# 1-Schematic_TRIAC_Dimmer.net
KiCad netlist of a schematic drawn in EasyEDA
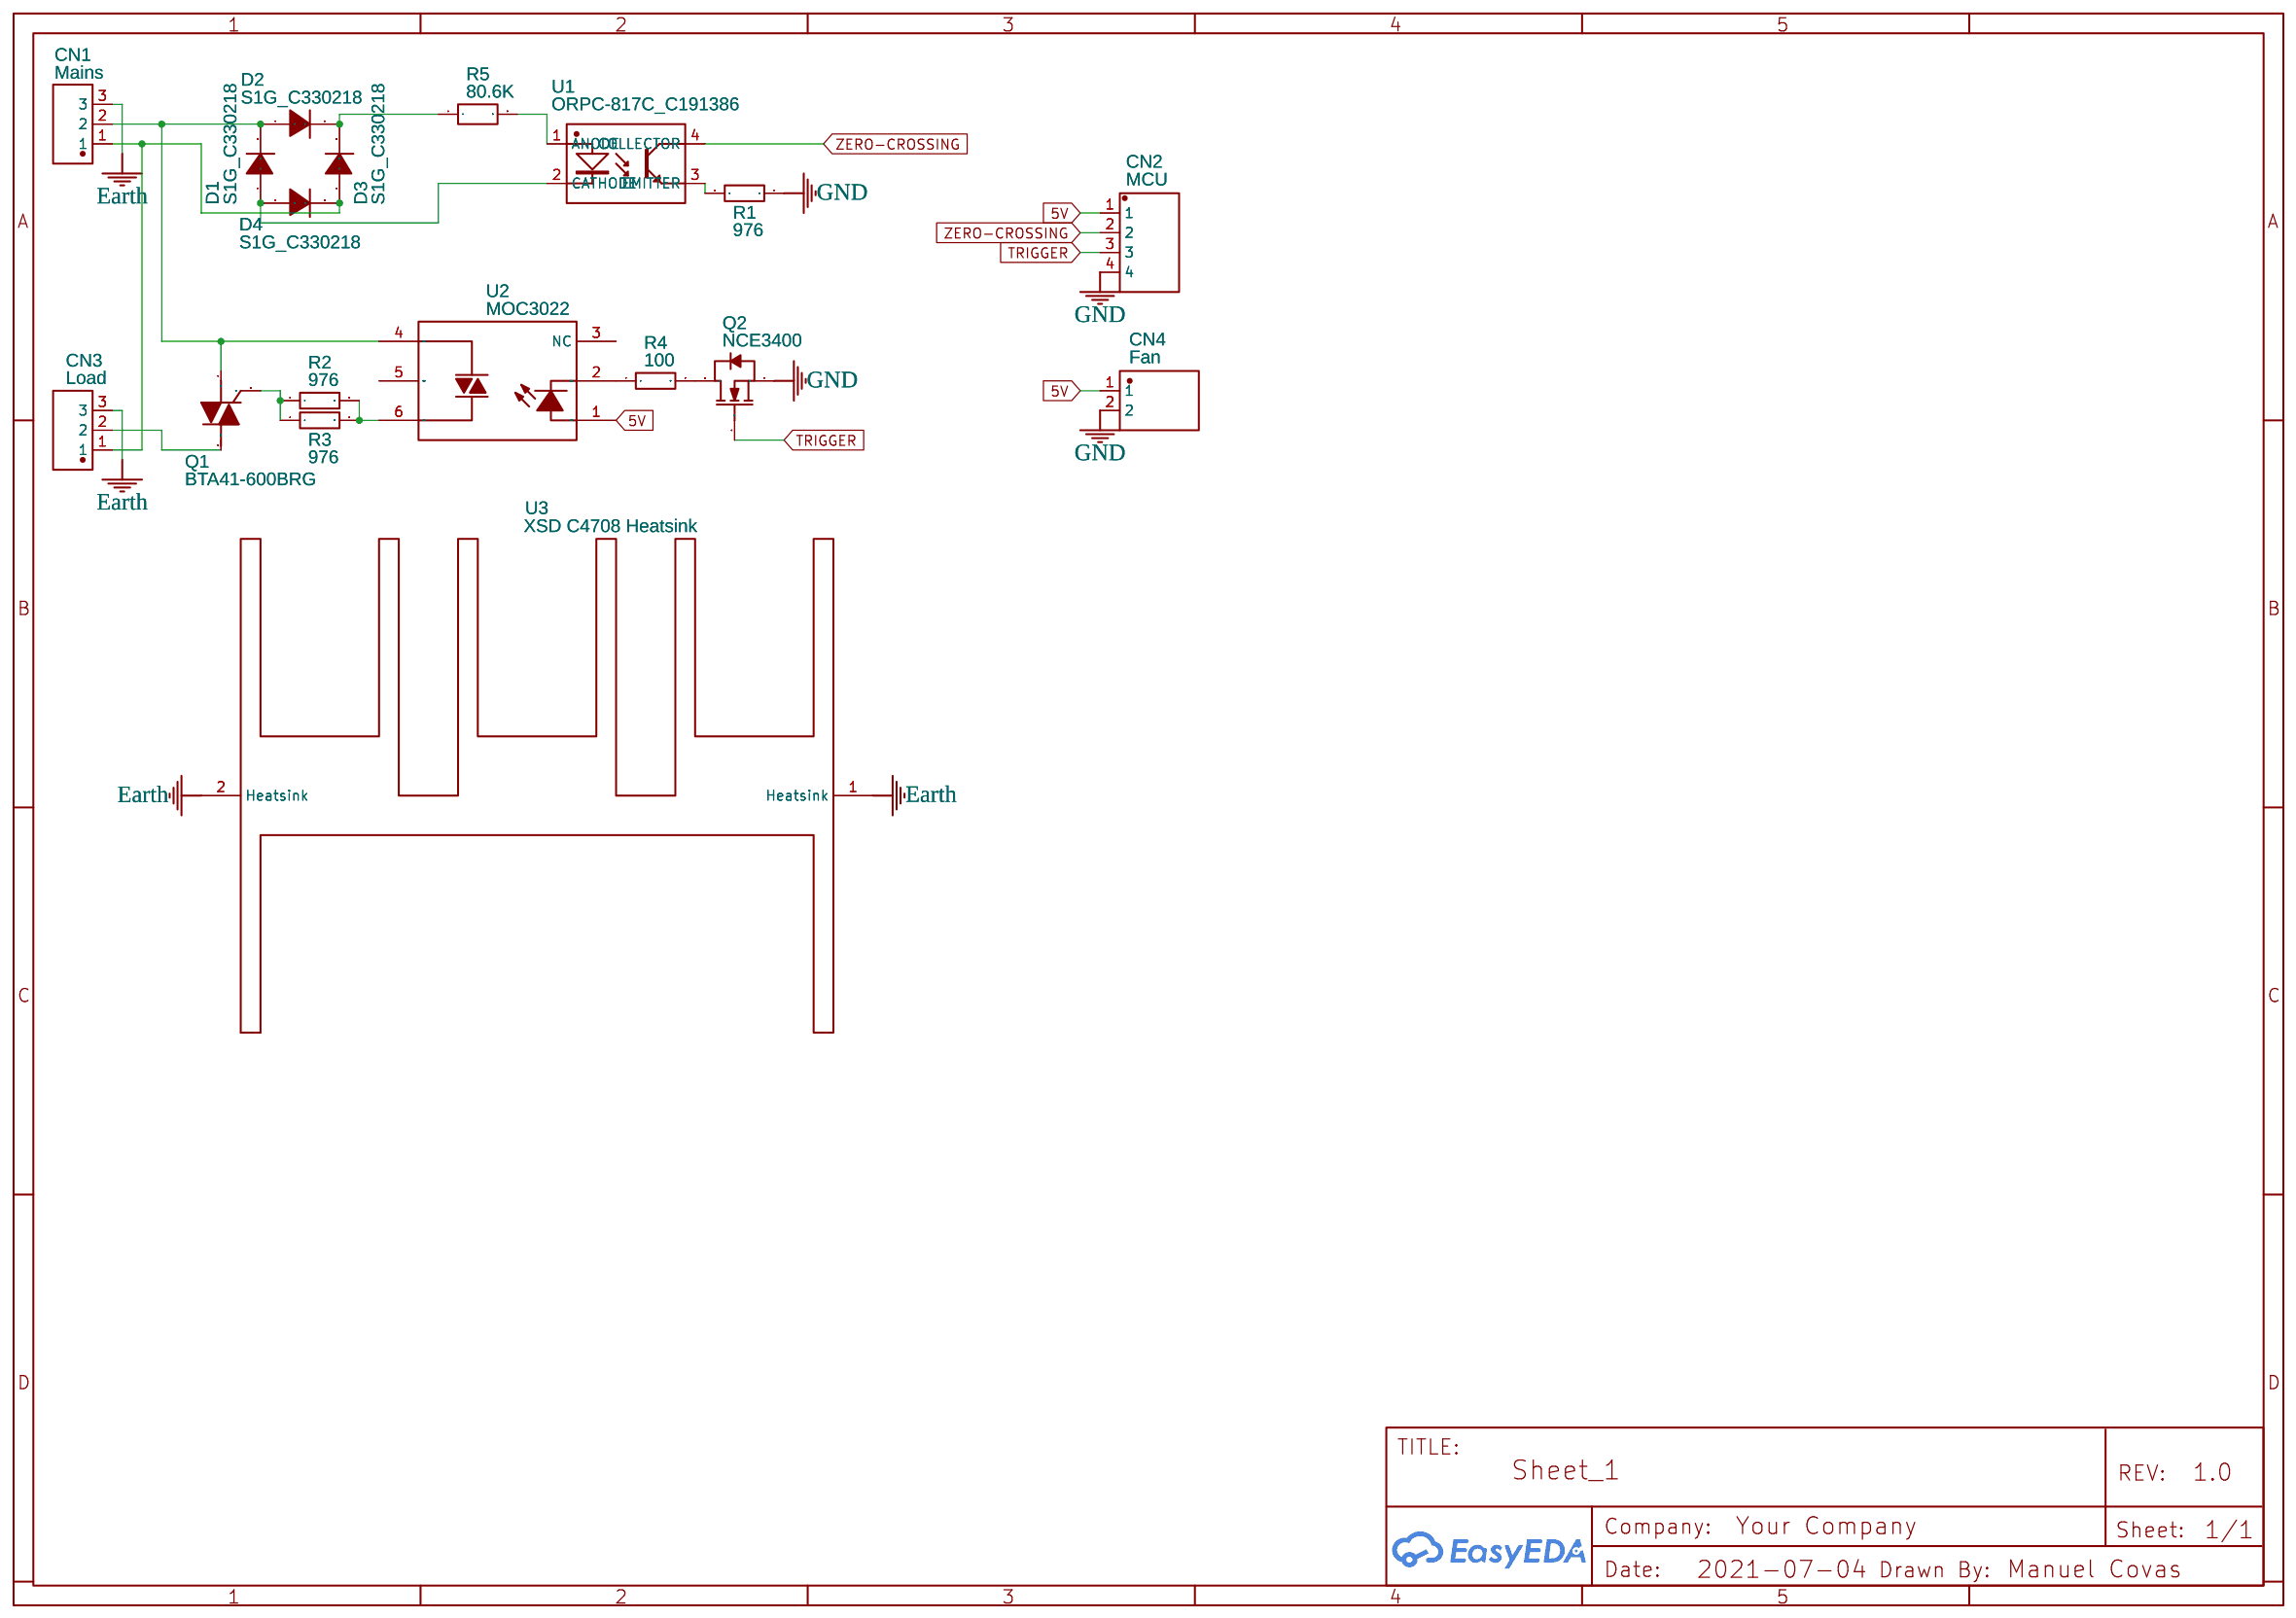
[diagram p0: schematic sheet]

(export (version "E")
  (design (tool "Eeschema 10.0.6"))
  (components
    (comp (ref "CN1")
      (value "Mains")
      (fields
        (field (name "BOM_Manufacturer Part") "KF301-5.0-3P")
        (field (name "BOM_Supplier Part") "C474882")
      )
      (libsource (lib "") (part "KF301-5.0-3P"))
    )
    (comp (ref "CN2")
      (value "MCU")
      (fields
        (field (name "BOM_Manufacturer Part") "B4B-XH-AM(LF)(SN)")
        (field (name "BOM_Supplier Part") "C161871")
      )
      (libsource (lib "") (part "B4B-XH-AM(LF)(SN)"))
    )
    (comp (ref "CN3")
      (value "Load")
      (fields
        (field (name "BOM_Manufacturer Part") "KF301-5.0-3P")
        (field (name "BOM_Supplier Part") "C474882")
      )
      (libsource (lib "") (part "KF301-5.0-3P"))
    )
    (comp (ref "CN4")
      (value "Fan")
      (fields (field (name "BOM_Supplier Part") "C161869"))
      (libsource (lib "") (part "B2B-XH-AM (LF)(SN)"))
    )
    (comp (ref "D1")
      (value "S1G_C330218")
      (fields (field (name "BOM_Supplier Part") "C330218"))
      (libsource (lib "") (part "S1G_C330218_1"))
    )
    (comp (ref "D2")
      (value "S1G_C330218")
      (fields (field (name "BOM_Supplier Part") "C330218"))
      (libsource (lib "") (part "S1G_C330218"))
    )
    (comp (ref "D3")
      (value "S1G_C330218")
      (fields (field (name "BOM_Supplier Part") "C330218"))
      (libsource (lib "") (part "S1G_C330218_1"))
    )
    (comp (ref "D4")
      (value "S1G_C330218")
      (fields (field (name "BOM_Supplier Part") "C330218"))
      (libsource (lib "") (part "S1G_C330218"))
    )
    (comp (ref "Q1")
      (value "BTA41-600BRG")
      (fields (field (name "BOM_Supplier Part") "C9103"))
      (libsource (lib "") (part "BTA41-600BRG"))
    )
    (comp (ref "Q2")
      (value "NCE3400")
      (fields (field (name "BOM_Supplier Part") "C113202"))
      (libsource (lib "") (part "NCE3400"))
    )
    (comp (ref "R1")
      (value "976")
      (fields
        (field (name "BOM_Manufacturer Part") "AC1206FR-07976RL")
        (field (name "BOM_Supplier Part") "C229856")
      )
      (libsource (lib "") (part "AC1206FR-07976RL_1"))
    )
    (comp (ref "R2")
      (value "976")
      (fields
        (field (name "BOM_Manufacturer Part") "AC1206FR-07976RL")
        (field (name "BOM_Supplier Part") "C229856")
      )
      (libsource (lib "") (part "AC1206FR-07976RL"))
    )
    (comp (ref "R3")
      (value "976")
      (fields
        (field (name "BOM_Manufacturer Part") "AC1206FR-07976RL")
        (field (name "BOM_Supplier Part") "C229856")
      )
      (libsource (lib "") (part "AC1206FR-07976RL"))
    )
    (comp (ref "R4")
      (value "100")
      (fields
        (field (name "BOM_Manufacturer Part") "RMC1/10K101FTP")
        (field (name "BOM_Supplier Part") "C340501")
      )
      (libsource (lib "") (part "RMC1/10K101FTP"))
    )
    (comp (ref "R5")
      (value "80.6K")
      (fields
        (field (name "BOM_Manufacturer Part") "25121WF8062T4E")
        (field (name "BOM_Supplier Part") "C406917")
      )
      (libsource (lib "") (part "25121WF8062T4E"))
    )
    (comp (ref "U1")
      (value "ORPC-817C_C191386")
      (fields (field (name "BOM_Manufacturer Part") "ORPC-817C") (field (name "BOM_Supplier Part") "C191386"))
      (libsource (lib "") (part "ORPC-817C_C191386"))
    )
    (comp (ref "U2")
      (value "MOC3022")
      (fields (field (name "BOM_Supplier Part") "C115466"))
      (libsource (lib "") (part "MOC3022"))
    )
    (comp (ref "U3")
      (value "XSD C4708 Heatsink")
      (fields (field (name "BOM_Manufacturer Part") "C4708"))
      (libsource (lib "") (part "XSD C4708 Heatsink"))
    )
  )
  (nets
    (net (code "1") (name "5V") (class "Default")
      (node (ref "CN2") (pin "1") (pinfunction "1_1") (pintype "unspecified"))
      (node (ref "CN4") (pin "1") (pinfunction "1_1") (pintype "unspecified"))
      (node (ref "U2") (pin "1") (pinfunction "ANODE_1") (pintype "unspecified"))
    )
    (net (code "2") (name "Earth") (class "Default")
      (node (ref "CN1") (pin "3") (pinfunction "3_3") (pintype "unspecified"))
      (node (ref "CN3") (pin "3") (pinfunction "3_3") (pintype "unspecified"))
      (node (ref "U3") (pin "1") (pinfunction "Heatsink_1") (pintype "unspecified"))
      (node (ref "U3") (pin "2") (pinfunction "Heatsink_2") (pintype "unspecified"))
    )
    (net (code "3") (name "GND") (class "Default")
      (node (ref "CN2") (pin "4") (pinfunction "4_4") (pintype "unspecified"))
      (node (ref "CN4") (pin "2") (pinfunction "2_2") (pintype "unspecified"))
      (node (ref "Q2") (pin "2") (pinfunction "S_2") (pintype "unspecified"))
      (node (ref "R1") (pin "1") (pinfunction "1_1") (pintype "unspecified"))
    )
    (net (code "4") (name "Net-(CN1-Pad1)") (class "Default")
      (node (ref "CN1") (pin "1") (pinfunction "1_1") (pintype "unspecified"))
      (node (ref "CN3") (pin "1") (pinfunction "1_1") (pintype "unspecified"))
      (node (ref "D3") (pin "1") (pinfunction "1_1") (pintype "unspecified"))
      (node (ref "D4") (pin "2") (pinfunction "2_2") (pintype "unspecified"))
    )
    (net (code "5") (name "Net-(D2-Pad2)") (class "Default")
      (node (ref "D2") (pin "2") (pinfunction "2_2") (pintype "unspecified"))
      (node (ref "D3") (pin "2") (pinfunction "2_2") (pintype "unspecified"))
      (node (ref "R5") (pin "1") (pinfunction "1_1") (pintype "unspecified"))
    )
    (net (code "6") (name "Net-(Q1-G)") (class "Default")
      (node (ref "Q1") (pin "3") (pinfunction "G_3") (pintype "unspecified"))
      (node (ref "R2") (pin "1") (pinfunction "1_1") (pintype "unspecified"))
      (node (ref "R3") (pin "1") (pinfunction "1_1") (pintype "unspecified"))
    )
    (net (code "7") (name "Net-(Q1-M1)") (class "Default")
      (node (ref "CN1") (pin "2") (pinfunction "2_2") (pintype "unspecified"))
      (node (ref "D1") (pin "2") (pinfunction "2_2") (pintype "unspecified"))
      (node (ref "D2") (pin "1") (pinfunction "1_1") (pintype "unspecified"))
      (node (ref "Q1") (pin "1") (pinfunction "M1_1") (pintype "unspecified"))
      (node (ref "U2") (pin "4") (pinfunction "_Terminal_4") (pintype "unspecified"))
    )
    (net (code "8") (name "Net-(Q1-M2)") (class "Default")
      (node (ref "CN3") (pin "2") (pinfunction "2_2") (pintype "unspecified"))
      (node (ref "Q1") (pin "2") (pinfunction "M2_2") (pintype "unspecified"))
    )
    (net (code "9") (name "Net-(Q2-D)") (class "Default")
      (node (ref "Q2") (pin "3") (pinfunction "D_3") (pintype "unspecified"))
      (node (ref "R4") (pin "2") (pinfunction "2_2") (pintype "unspecified"))
    )
    (net (code "10") (name "Net-(U1-ANODE)") (class "Default")
      (node (ref "R5") (pin "2") (pinfunction "2_2") (pintype "unspecified"))
      (node (ref "U1") (pin "1") (pinfunction "ANODE_1") (pintype "unspecified"))
    )
    (net (code "11") (name "Net-(U1-CATHODE)") (class "Default")
      (node (ref "D1") (pin "1") (pinfunction "1_1") (pintype "unspecified"))
      (node (ref "D4") (pin "1") (pinfunction "1_1") (pintype "unspecified"))
      (node (ref "U1") (pin "2") (pinfunction "CATHODE_2") (pintype "unspecified"))
    )
    (net (code "12") (name "Net-(U1-EMITTER)") (class "Default")
      (node (ref "R1") (pin "2") (pinfunction "2_2") (pintype "unspecified"))
      (node (ref "U1") (pin "3") (pinfunction "EMITTER_3") (pintype "unspecified"))
    )
    (net (code "13") (name "Net-(U2-Cathode_)") (class "Default")
      (node (ref "R4") (pin "1") (pinfunction "1_1") (pintype "unspecified"))
      (node (ref "U2") (pin "2") (pinfunction "Cathode__2") (pintype "unspecified"))
    )
    (net (code "14") (name "Net-(U2-Terminal_)") (class "Default")
      (node (ref "R2") (pin "2") (pinfunction "2_2") (pintype "unspecified"))
      (node (ref "R3") (pin "2") (pinfunction "2_2") (pintype "unspecified"))
      (node (ref "U2") (pin "6") (pinfunction "Terminal__6") (pintype "unspecified"))
    )
    (net (code "15") (name "TRIGGER") (class "Default")
      (node (ref "CN2") (pin "3") (pinfunction "3_3") (pintype "unspecified"))
      (node (ref "Q2") (pin "1") (pinfunction "G_1") (pintype "unspecified"))
    )
    (net (code "16") (name "ZERO-CROSSING") (class "Default")
      (node (ref "CN2") (pin "2") (pinfunction "2_2") (pintype "unspecified"))
      (node (ref "U1") (pin "4") (pinfunction "COLLECTOR_4") (pintype "unspecified"))
    )
    (net (code "17") (name "unconnected-(U2-NC-Pad3)") (class "Default")
      (node (ref "U2") (pin "3") (pinfunction "NC_3") (pintype "unspecified"))
    )
    (net (code "18") (name "unconnected-(U2-Substrate_-Pad5)") (class "Default")
      (node (ref "U2") (pin "5") (pinfunction "Substrate__5") (pintype "unspecified"))
    )
  )
)
